# draft3_4lyr_reroute.net
KiCad netlist of a schematic drawn in EAGLE
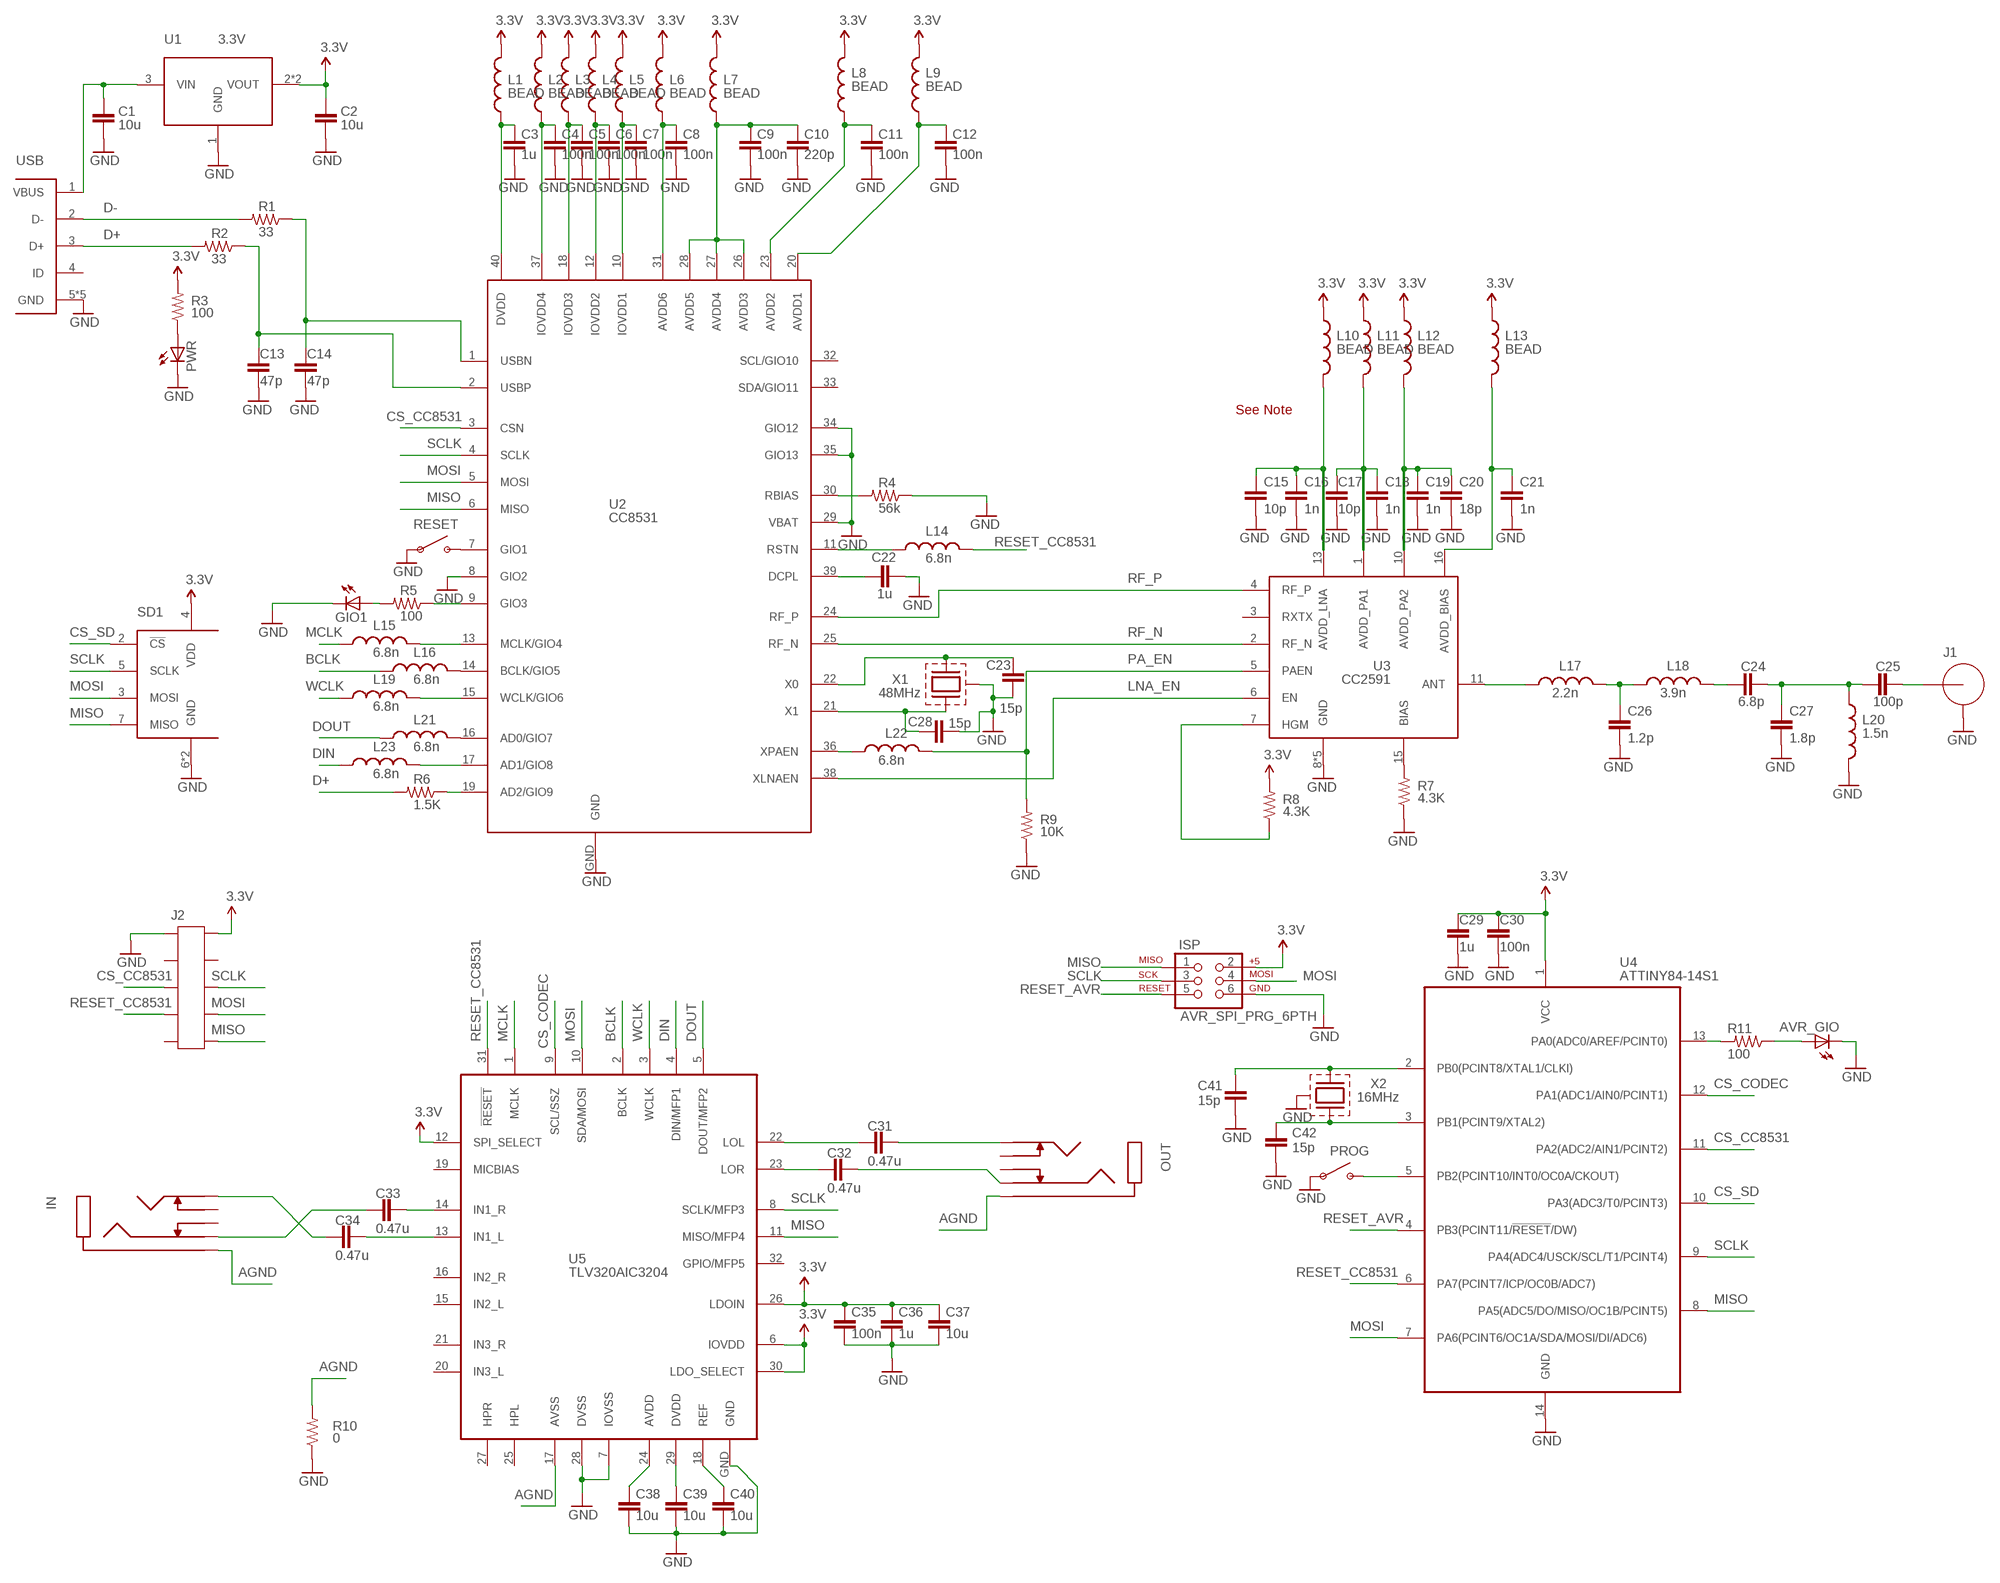
[diagram p0: schematic, sheet 1]

(export (version "E")
  (design (tool "Eeschema 10.0.6"))
  (components
    (comp (ref "AVR_GIO")
      (value "LEDCHIP-LED0603")
      (footprint "eagle-import:CHIP-LED0603")
      (libsource (lib "eagle-import") (part "LEDCHIP-LED0603"))
    )
    (comp (ref "C1")
      (value "10u")
      (footprint "eagle-import:C0603")
      (libsource (lib "eagle-import") (part "C-EUC0603"))
    )
    (comp (ref "C2")
      (value "10u")
      (footprint "eagle-import:C0603")
      (libsource (lib "eagle-import") (part "C-EUC0603"))
    )
    (comp (ref "C3")
      (value "1u")
      (footprint "eagle-import:C0603")
      (libsource (lib "eagle-import") (part "C-EUC0603"))
    )
    (comp (ref "C4")
      (value "100n")
      (footprint "eagle-import:C0603")
      (libsource (lib "eagle-import") (part "C-EUC0603"))
    )
    (comp (ref "C5")
      (value "100n")
      (footprint "eagle-import:C0603")
      (libsource (lib "eagle-import") (part "C-EUC0603"))
    )
    (comp (ref "C6")
      (value "100n")
      (footprint "eagle-import:C0603")
      (libsource (lib "eagle-import") (part "C-EUC0603"))
    )
    (comp (ref "C7")
      (value "100n")
      (footprint "eagle-import:C0603")
      (libsource (lib "eagle-import") (part "C-EUC0603"))
    )
    (comp (ref "C8")
      (value "100n")
      (footprint "eagle-import:C0603")
      (libsource (lib "eagle-import") (part "C-EUC0603"))
    )
    (comp (ref "C9")
      (value "100n")
      (footprint "eagle-import:C0603")
      (libsource (lib "eagle-import") (part "C-EUC0603"))
    )
    (comp (ref "C10")
      (value "220p")
      (footprint "eagle-import:C0603")
      (libsource (lib "eagle-import") (part "C-EUC0603"))
    )
    (comp (ref "C11")
      (value "100n")
      (footprint "eagle-import:C0603")
      (libsource (lib "eagle-import") (part "C-EUC0603"))
    )
    (comp (ref "C12")
      (value "100n")
      (footprint "eagle-import:C0603")
      (libsource (lib "eagle-import") (part "C-EUC0603"))
    )
    (comp (ref "C13")
      (value "47p")
      (footprint "eagle-import:C0603")
      (libsource (lib "eagle-import") (part "C-EUC0603"))
    )
    (comp (ref "C14")
      (value "47p")
      (footprint "eagle-import:C0603")
      (libsource (lib "eagle-import") (part "C-EUC0603"))
    )
    (comp (ref "C15")
      (value "10p")
      (footprint "eagle-import:C0603")
      (libsource (lib "eagle-import") (part "C-EUC0603"))
    )
    (comp (ref "C16")
      (value "1n")
      (footprint "eagle-import:C0603")
      (libsource (lib "eagle-import") (part "C-EUC0603"))
    )
    (comp (ref "C17")
      (value "10p")
      (footprint "eagle-import:C0603")
      (libsource (lib "eagle-import") (part "C-EUC0603"))
    )
    (comp (ref "C18")
      (value "1n")
      (footprint "eagle-import:C0603")
      (libsource (lib "eagle-import") (part "C-EUC0603"))
    )
    (comp (ref "C19")
      (value "1n")
      (footprint "eagle-import:C0603")
      (libsource (lib "eagle-import") (part "C-EUC0603"))
    )
    (comp (ref "C20")
      (value "18p")
      (footprint "eagle-import:C0603")
      (libsource (lib "eagle-import") (part "C-EUC0603"))
    )
    (comp (ref "C21")
      (value "1n")
      (footprint "eagle-import:C0603")
      (libsource (lib "eagle-import") (part "C-EUC0603"))
    )
    (comp (ref "C22")
      (value "1u")
      (footprint "eagle-import:C0603")
      (libsource (lib "eagle-import") (part "C-EUC0603"))
    )
    (comp (ref "C23")
      (value "15p")
      (footprint "eagle-import:C0603")
      (libsource (lib "eagle-import") (part "C-EUC0603"))
    )
    (comp (ref "C24")
      (value "6.8p")
      (footprint "eagle-import:C0603")
      (libsource (lib "eagle-import") (part "C-EUC0603"))
    )
    (comp (ref "C25")
      (value "100p")
      (footprint "eagle-import:C0603")
      (libsource (lib "eagle-import") (part "C-EUC0603"))
    )
    (comp (ref "C26")
      (value "1.2p")
      (footprint "eagle-import:C0603")
      (libsource (lib "eagle-import") (part "C-EUC0603"))
    )
    (comp (ref "C27")
      (value "1.8p")
      (footprint "eagle-import:C0603")
      (libsource (lib "eagle-import") (part "C-EUC0603"))
    )
    (comp (ref "C28")
      (value "15p")
      (footprint "eagle-import:C0603")
      (libsource (lib "eagle-import") (part "C-EUC0603"))
    )
    (comp (ref "C29")
      (value "1u")
      (footprint "eagle-import:C0603")
      (libsource (lib "eagle-import") (part "C-EUC0603"))
    )
    (comp (ref "C30")
      (value "100n")
      (footprint "eagle-import:C0603")
      (libsource (lib "eagle-import") (part "C-EUC0603"))
    )
    (comp (ref "C31")
      (value "0.47u")
      (footprint "eagle-import:C0603")
      (libsource (lib "eagle-import") (part "C-EUC0603"))
    )
    (comp (ref "C32")
      (value "0.47u")
      (footprint "eagle-import:C0603")
      (libsource (lib "eagle-import") (part "C-EUC0603"))
    )
    (comp (ref "C33")
      (value "0.47u")
      (footprint "eagle-import:C0603")
      (libsource (lib "eagle-import") (part "C-EUC0603"))
    )
    (comp (ref "C34")
      (value "0.47u")
      (footprint "eagle-import:C0603")
      (libsource (lib "eagle-import") (part "C-EUC0603"))
    )
    (comp (ref "C35")
      (value "100n")
      (footprint "eagle-import:C0603")
      (libsource (lib "eagle-import") (part "C-EUC0603"))
    )
    (comp (ref "C36")
      (value "1u")
      (footprint "eagle-import:C0603")
      (libsource (lib "eagle-import") (part "C-EUC0603"))
    )
    (comp (ref "C37")
      (value "10u")
      (footprint "eagle-import:C0603")
      (libsource (lib "eagle-import") (part "C-EUC0603"))
    )
    (comp (ref "C38")
      (value "10u")
      (footprint "eagle-import:C0603")
      (libsource (lib "eagle-import") (part "C-EUC0603"))
    )
    (comp (ref "C39")
      (value "10u")
      (footprint "eagle-import:C0603")
      (libsource (lib "eagle-import") (part "C-EUC0603"))
    )
    (comp (ref "C40")
      (value "10u")
      (footprint "eagle-import:C0603")
      (libsource (lib "eagle-import") (part "C-EUC0603"))
    )
    (comp (ref "C41")
      (value "15p")
      (footprint "eagle-import:C0603")
      (libsource (lib "eagle-import") (part "C-EUC0603"))
    )
    (comp (ref "C42")
      (value "15p")
      (footprint "eagle-import:C0603")
      (libsource (lib "eagle-import") (part "C-EUC0603"))
    )
    (comp (ref "GIO1")
      (value "LEDCHIP-LED0603")
      (footprint "eagle-import:CHIP-LED0603")
      (libsource (lib "eagle-import") (part "LEDCHIP-LED0603"))
    )
    (comp (ref "IN")
      (value "PHONE_SW")
      (footprint "eagle-import:35RAPC4BV4")
      (libsource (lib "eagle-import") (part "PHONE_SW"))
    )
    (comp (ref "ISP")
      (value "AVR_SPI_PRG_6PTH")
      (footprint "eagle-import:2X3")
      (libsource (lib "eagle-import") (part "AVR_SPI_PRG_6PTH"))
    )
    (comp (ref "J1")
      (value "SMA")
      (footprint "eagle-import:CONSMA003.031")
      (libsource (lib "eagle-import") (part "SMA"))
    )
    (comp (ref "J2")
      (value "HEADER-10P-SMD-MALE")
      (footprint "eagle-import:10P-0.05-HEADER")
      (libsource (lib "eagle-import") (part "HEADER-10P-SMD-MALE"))
    )
    (comp (ref "L1")
      (value "BEAD")
      (footprint "eagle-import:0603")
      (libsource (lib "eagle-import") (part "INDUCTOR0603"))
    )
    (comp (ref "L2")
      (value "BEAD")
      (footprint "eagle-import:0603")
      (libsource (lib "eagle-import") (part "INDUCTOR0603"))
    )
    (comp (ref "L3")
      (value "BEAD")
      (footprint "eagle-import:0603")
      (libsource (lib "eagle-import") (part "INDUCTOR0603"))
    )
    (comp (ref "L4")
      (value "BEAD")
      (footprint "eagle-import:0603")
      (libsource (lib "eagle-import") (part "INDUCTOR0603"))
    )
    (comp (ref "L5")
      (value "BEAD")
      (footprint "eagle-import:0603")
      (libsource (lib "eagle-import") (part "INDUCTOR0603"))
    )
    (comp (ref "L6")
      (value "BEAD")
      (footprint "eagle-import:0603")
      (libsource (lib "eagle-import") (part "INDUCTOR0603"))
    )
    (comp (ref "L7")
      (value "BEAD")
      (footprint "eagle-import:0603")
      (libsource (lib "eagle-import") (part "INDUCTOR0603"))
    )
    (comp (ref "L8")
      (value "BEAD")
      (footprint "eagle-import:0603")
      (libsource (lib "eagle-import") (part "INDUCTOR0603"))
    )
    (comp (ref "L9")
      (value "BEAD")
      (footprint "eagle-import:0603")
      (libsource (lib "eagle-import") (part "INDUCTOR0603"))
    )
    (comp (ref "L10")
      (value "BEAD")
      (footprint "eagle-import:0603")
      (libsource (lib "eagle-import") (part "INDUCTOR0603"))
    )
    (comp (ref "L11")
      (value "BEAD")
      (footprint "eagle-import:0603")
      (libsource (lib "eagle-import") (part "INDUCTOR0603"))
    )
    (comp (ref "L12")
      (value "BEAD")
      (footprint "eagle-import:0603")
      (libsource (lib "eagle-import") (part "INDUCTOR0603"))
    )
    (comp (ref "L13")
      (value "BEAD")
      (footprint "eagle-import:0603")
      (libsource (lib "eagle-import") (part "INDUCTOR0603"))
    )
    (comp (ref "L14")
      (value "6.8n")
      (footprint "eagle-import:0603")
      (libsource (lib "eagle-import") (part "INDUCTOR0603"))
    )
    (comp (ref "L15")
      (value "6.8n")
      (footprint "eagle-import:0603")
      (libsource (lib "eagle-import") (part "INDUCTOR0603"))
    )
    (comp (ref "L16")
      (value "6.8n")
      (footprint "eagle-import:0603")
      (libsource (lib "eagle-import") (part "INDUCTOR0603"))
    )
    (comp (ref "L17")
      (value "2.2n")
      (footprint "eagle-import:0603")
      (libsource (lib "eagle-import") (part "INDUCTOR0603"))
    )
    (comp (ref "L18")
      (value "3.9n")
      (footprint "eagle-import:0603")
      (libsource (lib "eagle-import") (part "INDUCTOR0603"))
    )
    (comp (ref "L19")
      (value "6.8n")
      (footprint "eagle-import:0603")
      (libsource (lib "eagle-import") (part "INDUCTOR0603"))
    )
    (comp (ref "L20")
      (value "1.5n")
      (footprint "eagle-import:0603")
      (libsource (lib "eagle-import") (part "INDUCTOR0603"))
    )
    (comp (ref "L21")
      (value "6.8n")
      (footprint "eagle-import:0603")
      (libsource (lib "eagle-import") (part "INDUCTOR0603"))
    )
    (comp (ref "L22")
      (value "6.8n")
      (footprint "eagle-import:0603")
      (libsource (lib "eagle-import") (part "INDUCTOR0603"))
    )
    (comp (ref "L23")
      (value "6.8n")
      (footprint "eagle-import:0603")
      (libsource (lib "eagle-import") (part "INDUCTOR0603"))
    )
    (comp (ref "OUT")
      (value "PHONE_SW")
      (footprint "eagle-import:35RAPC4BV4")
      (libsource (lib "eagle-import") (part "PHONE_SW"))
    )
    (comp (ref "PROG")
      (value "SPST-SMD")
      (footprint "eagle-import:TACT_SW")
      (libsource (lib "eagle-import") (part "SPST-SMD"))
    )
    (comp (ref "PWR")
      (value "LEDCHIP-LED0603")
      (footprint "eagle-import:CHIP-LED0603")
      (libsource (lib "eagle-import") (part "LEDCHIP-LED0603"))
    )
    (comp (ref "R1")
      (value "33")
      (footprint "eagle-import:R0603")
      (libsource (lib "eagle-import") (part "R-US_R0603"))
    )
    (comp (ref "R2")
      (value "33")
      (footprint "eagle-import:R0603")
      (libsource (lib "eagle-import") (part "R-US_R0603"))
    )
    (comp (ref "R3")
      (value "100")
      (footprint "eagle-import:R0603")
      (libsource (lib "eagle-import") (part "R-US_R0603"))
    )
    (comp (ref "R4")
      (value "56k")
      (footprint "eagle-import:R0603")
      (libsource (lib "eagle-import") (part "R-US_R0603"))
    )
    (comp (ref "R5")
      (value "100")
      (footprint "eagle-import:R0603")
      (libsource (lib "eagle-import") (part "R-US_R0603"))
    )
    (comp (ref "R6")
      (value "1.5K")
      (footprint "eagle-import:R0603")
      (libsource (lib "eagle-import") (part "R-US_R0603"))
    )
    (comp (ref "R7")
      (value "4.3K")
      (footprint "eagle-import:R0603")
      (libsource (lib "eagle-import") (part "R-US_R0603"))
    )
    (comp (ref "R8")
      (value "4.3K")
      (footprint "eagle-import:R0603")
      (libsource (lib "eagle-import") (part "R-US_R0603"))
    )
    (comp (ref "R9")
      (value "10K")
      (footprint "eagle-import:R0603")
      (libsource (lib "eagle-import") (part "R-US_R0603"))
    )
    (comp (ref "R10")
      (value "0")
      (footprint "eagle-import:R0603")
      (libsource (lib "eagle-import") (part "R-US_R0603"))
    )
    (comp (ref "R11")
      (value "100")
      (footprint "eagle-import:R0603")
      (libsource (lib "eagle-import") (part "R-US_R0603"))
    )
    (comp (ref "RESET")
      (value "SPST-SMD")
      (footprint "eagle-import:TACT_SW")
      (libsource (lib "eagle-import") (part "SPST-SMD"))
    )
    (comp (ref "SD1")
      (value "MICROSDDM3AT")
      (footprint "eagle-import:DM3AT")
      (libsource (lib "eagle-import") (part "MICROSDDM3AT"))
    )
    (comp (ref "U1")
      (value "3.3V")
      (footprint "eagle-import:SOT-223")
      (libsource (lib "eagle-import") (part "NX1117C"))
    )
    (comp (ref "U2")
      (value "CC8531")
      (footprint "eagle-import:S-PVQFN-N40")
      (libsource (lib "eagle-import") (part "CC8531"))
    )
    (comp (ref "U3")
      (value "CC2591")
      (footprint "eagle-import:S-PVQFN-N16")
      (libsource (lib "eagle-import") (part "CC2591"))
    )
    (comp (ref "U4")
      (value "ATTINY84-14S1")
      (footprint "eagle-import:SOIC14")
      (libsource (lib "eagle-import") (part "ATTINY84-14S1"))
    )
    (comp (ref "U5")
      (value "TLV320AIC3204")
      (footprint "eagle-import:S-PVQFN-N32")
      (libsource (lib "eagle-import") (part "TLV320AIC3204"))
    )
    (comp (ref "USB")
      (value "USB_MICRO_AB")
      (footprint "eagle-import:USB_MICRO_AB")
      (libsource (lib "eagle-import") (part "USB_MICRO_AB"))
    )
    (comp (ref "X1")
      (value "48MHz")
      (footprint "eagle-import:ABM3C")
      (libsource (lib "eagle-import") (part "XTAL-ABRACONABM3C"))
    )
    (comp (ref "X2")
      (value "16MHz")
      (footprint "eagle-import:ABMM")
      (libsource (lib "eagle-import") (part "XTAL-ABRACONABMM"))
    )
  )
  (nets
    (net (code "1") (name "/AGND") (class "Default")
      (node (ref "IN") (pin "1") (pinfunction "GND_1") (pintype "bidirectional"))
      (node (ref "OUT") (pin "1") (pinfunction "GND_1") (pintype "bidirectional"))
      (node (ref "R10") (pin "2") (pinfunction "2_2") (pintype "passive"))
      (node (ref "U5") (pin "17") (pinfunction "AVSS_17") (pintype "bidirectional"))
    )
    (net (code "2") (name "/BCLK") (class "Default")
      (node (ref "L16") (pin "1") (pinfunction "1_1") (pintype "passive"))
      (node (ref "U5") (pin "2") (pinfunction "BCLK_2") (pintype "bidirectional"))
    )
    (net (code "3") (name "/CS_CC8531") (class "Default")
      (node (ref "J2") (pin "5") (pinfunction "5_5") (pintype "bidirectional"))
      (node (ref "U2") (pin "3") (pinfunction "CSN_3") (pintype "bidirectional"))
      (node (ref "U4") (pin "11") (pinfunction "PA2(ADC2/AIN1/PCINT2)_11") (pintype "bidirectional"))
    )
    (net (code "4") (name "/CS_CODEC") (class "Default")
      (node (ref "U4") (pin "12") (pinfunction "PA1(ADC1/AIN0/PCINT1)_12") (pintype "bidirectional"))
      (node (ref "U5") (pin "9") (pinfunction "SCL/SSZ_9") (pintype "bidirectional"))
    )
    (net (code "5") (name "/CS_SD") (class "Default")
      (node (ref "SD1") (pin "2") (pinfunction "~{CS}_2") (pintype "bidirectional"))
      (node (ref "U4") (pin "10") (pinfunction "PA3(ADC3/T0/PCINT3)_10") (pintype "bidirectional"))
    )
    (net (code "6") (name "/D+") (class "Default")
      (node (ref "R2") (pin "2") (pinfunction "2_2") (pintype "passive"))
      (node (ref "R6") (pin "2") (pinfunction "2_2") (pintype "passive"))
      (node (ref "USB") (pin "3") (pinfunction "D+_3") (pintype "bidirectional"))
    )
    (net (code "7") (name "/D-") (class "Default")
      (node (ref "R1") (pin "2") (pinfunction "2_2") (pintype "passive"))
      (node (ref "USB") (pin "2") (pinfunction "D-_2") (pintype "bidirectional"))
    )
    (net (code "8") (name "/DIN") (class "Default")
      (node (ref "L23") (pin "1") (pinfunction "1_1") (pintype "passive"))
      (node (ref "U5") (pin "4") (pinfunction "DIN/MFP1_4") (pintype "bidirectional"))
    )
    (net (code "9") (name "/DOUT") (class "Default")
      (node (ref "L21") (pin "1") (pinfunction "1_1") (pintype "passive"))
      (node (ref "U5") (pin "5") (pinfunction "DOUT/MFP2_5") (pintype "bidirectional"))
    )
    (net (code "10") (name "/LNA_EN") (class "Default")
      (node (ref "U2") (pin "38") (pinfunction "XLNAEN_38") (pintype "bidirectional"))
      (node (ref "U3") (pin "6") (pinfunction "EN_6") (pintype "bidirectional"))
    )
    (net (code "11") (name "/MCLK") (class "Default")
      (node (ref "L15") (pin "1") (pinfunction "1_1") (pintype "passive"))
      (node (ref "U5") (pin "1") (pinfunction "MCLK_1") (pintype "bidirectional"))
    )
    (net (code "12") (name "/MISO") (class "Default")
      (node (ref "ISP") (pin "1") (pinfunction "1_1") (pintype "passive"))
      (node (ref "J2") (pin "10") (pinfunction "10_10") (pintype "bidirectional"))
      (node (ref "SD1") (pin "7") (pinfunction "MISO_7") (pintype "bidirectional"))
      (node (ref "U2") (pin "6") (pinfunction "MISO_6") (pintype "bidirectional"))
      (node (ref "U4") (pin "8") (pinfunction "PA5(ADC5/DO/MISO/OC1B/PCINT5)_8") (pintype "bidirectional"))
      (node (ref "U5") (pin "11") (pinfunction "MISO/MFP4_11") (pintype "bidirectional"))
    )
    (net (code "13") (name "/MOSI") (class "Default")
      (node (ref "ISP") (pin "4") (pinfunction "4_4") (pintype "passive"))
      (node (ref "J2") (pin "8") (pinfunction "8_8") (pintype "bidirectional"))
      (node (ref "SD1") (pin "3") (pinfunction "MOSI_3") (pintype "bidirectional"))
      (node (ref "U2") (pin "5") (pinfunction "MOSI_5") (pintype "bidirectional"))
      (node (ref "U4") (pin "7") (pinfunction "PA6(PCINT6/OC1A/SDA/MOSI/DI/ADC6)_7") (pintype "bidirectional"))
      (node (ref "U5") (pin "10") (pinfunction "SDA/MOSI_10") (pintype "bidirectional"))
    )
    (net (code "14") (name "/PA_EN") (class "Default")
      (node (ref "L22") (pin "2") (pinfunction "2_2") (pintype "passive"))
      (node (ref "R9") (pin "2") (pinfunction "2_2") (pintype "passive"))
      (node (ref "U3") (pin "5") (pinfunction "PAEN_5") (pintype "bidirectional"))
    )
    (net (code "15") (name "/RESET_AVR") (class "Default")
      (node (ref "ISP") (pin "5") (pinfunction "5_5") (pintype "passive"))
      (node (ref "U4") (pin "4") (pinfunction "PB3(PCINT11/~{RESET}/DW)_4") (pintype "bidirectional"))
    )
    (net (code "16") (name "/RESET_CC8531") (class "Default")
      (node (ref "J2") (pin "7") (pinfunction "7_7") (pintype "bidirectional"))
      (node (ref "L14") (pin "2") (pinfunction "2_2") (pintype "passive"))
      (node (ref "U4") (pin "6") (pinfunction "PA7(PCINT7/ICP/OC0B/ADC7)_6") (pintype "bidirectional"))
      (node (ref "U5") (pin "31") (pinfunction "~{RESET}_31") (pintype "bidirectional"))
    )
    (net (code "17") (name "/RF_N") (class "Default")
      (node (ref "U2") (pin "25") (pinfunction "RF_N_25") (pintype "bidirectional"))
      (node (ref "U3") (pin "2") (pinfunction "RF_N_2") (pintype "bidirectional"))
    )
    (net (code "18") (name "/RF_P") (class "Default")
      (node (ref "U2") (pin "24") (pinfunction "RF_P_24") (pintype "bidirectional"))
      (node (ref "U3") (pin "4") (pinfunction "RF_P_4") (pintype "bidirectional"))
    )
    (net (code "19") (name "/SCLK") (class "Default")
      (node (ref "ISP") (pin "3") (pinfunction "3_3") (pintype "passive"))
      (node (ref "J2") (pin "6") (pinfunction "6_6") (pintype "bidirectional"))
      (node (ref "SD1") (pin "5") (pinfunction "SCLK_5") (pintype "bidirectional"))
      (node (ref "U2") (pin "4") (pinfunction "SCLK_4") (pintype "bidirectional"))
      (node (ref "U4") (pin "9") (pinfunction "PA4(ADC4/USCK/SCL/T1/PCINT4)_9") (pintype "bidirectional"))
      (node (ref "U5") (pin "8") (pinfunction "SCLK/MFP3_8") (pintype "bidirectional"))
    )
    (net (code "20") (name "/WCLK") (class "Default")
      (node (ref "L19") (pin "1") (pinfunction "1_1") (pintype "passive"))
      (node (ref "U5") (pin "3") (pinfunction "WCLK_3") (pintype "bidirectional"))
    )
    (net (code "21") (name "3.3V") (class "Default")
      (node (ref "C2") (pin "1") (pinfunction "1_1") (pintype "passive"))
      (node (ref "C29") (pin "1") (pinfunction "1_1") (pintype "passive"))
      (node (ref "C30") (pin "1") (pinfunction "1_1") (pintype "passive"))
      (node (ref "C35") (pin "1") (pinfunction "1_1") (pintype "passive"))
      (node (ref "C36") (pin "1") (pinfunction "1_1") (pintype "passive"))
      (node (ref "C37") (pin "1") (pinfunction "1_1") (pintype "passive"))
      (node (ref "ISP") (pin "2") (pinfunction "2_2") (pintype "passive"))
      (node (ref "J2") (pin "2") (pinfunction "2_2") (pintype "bidirectional"))
      (node (ref "L1") (pin "2") (pinfunction "2_2") (pintype "passive"))
      (node (ref "L10") (pin "1") (pinfunction "1_1") (pintype "passive"))
      (node (ref "L11") (pin "1") (pinfunction "1_1") (pintype "passive"))
      (node (ref "L12") (pin "1") (pinfunction "1_1") (pintype "passive"))
      (node (ref "L13") (pin "1") (pinfunction "1_1") (pintype "passive"))
      (node (ref "L2") (pin "2") (pinfunction "2_2") (pintype "passive"))
      (node (ref "L3") (pin "2") (pinfunction "2_2") (pintype "passive"))
      (node (ref "L4") (pin "2") (pinfunction "2_2") (pintype "passive"))
      (node (ref "L5") (pin "2") (pinfunction "2_2") (pintype "passive"))
      (node (ref "L6") (pin "2") (pinfunction "2_2") (pintype "passive"))
      (node (ref "L7") (pin "2") (pinfunction "2_2") (pintype "passive"))
      (node (ref "L8") (pin "2") (pinfunction "2_2") (pintype "passive"))
      (node (ref "L9") (pin "2") (pinfunction "2_2") (pintype "passive"))
      (node (ref "R3") (pin "2") (pinfunction "2_2") (pintype "passive"))
      (node (ref "R8") (pin "2") (pinfunction "2_2") (pintype "passive"))
      (node (ref "SD1") (pin "4") (pinfunction "VDD_4") (pintype "bidirectional"))
      (node (ref "U1") (pin "2") (pinfunction "VOUT_2") (pintype "bidirectional"))
      (node (ref "U1") (pin "4") (pinfunction "VOUT_4") (pintype "bidirectional"))
      (node (ref "U4") (pin "1") (pinfunction "VCC_1") (pintype "bidirectional"))
      (node (ref "U5") (pin "12") (pinfunction "SPI_SELECT_12") (pintype "bidirectional"))
      (node (ref "U5") (pin "26") (pinfunction "LDOIN_26") (pintype "bidirectional"))
      (node (ref "U5") (pin "30") (pinfunction "LDO_SELECT_30") (pintype "bidirectional"))
      (node (ref "U5") (pin "6") (pinfunction "IOVDD_6") (pintype "bidirectional"))
    )
    (net (code "22") (name "GND") (class "Default")
      (node (ref "AVR_GIO") (pin "C") (pinfunction "C_C") (pintype "passive"))
      (node (ref "C1") (pin "2") (pinfunction "2_2") (pintype "passive"))
      (node (ref "C10") (pin "2") (pinfunction "2_2") (pintype "passive"))
      (node (ref "C11") (pin "2") (pinfunction "2_2") (pintype "passive"))
      (node (ref "C12") (pin "2") (pinfunction "2_2") (pintype "passive"))
      (node (ref "C13") (pin "2") (pinfunction "2_2") (pintype "passive"))
      (node (ref "C14") (pin "2") (pinfunction "2_2") (pintype "passive"))
      (node (ref "C15") (pin "2") (pinfunction "2_2") (pintype "passive"))
      (node (ref "C16") (pin "2") (pinfunction "2_2") (pintype "passive"))
      (node (ref "C17") (pin "2") (pinfunction "2_2") (pintype "passive"))
      (node (ref "C18") (pin "2") (pinfunction "2_2") (pintype "passive"))
      (node (ref "C19") (pin "2") (pinfunction "2_2") (pintype "passive"))
      (node (ref "C2") (pin "2") (pinfunction "2_2") (pintype "passive"))
      (node (ref "C20") (pin "2") (pinfunction "2_2") (pintype "passive"))
      (node (ref "C21") (pin "2") (pinfunction "2_2") (pintype "passive"))
      (node (ref "C22") (pin "2") (pinfunction "2_2") (pintype "passive"))
      (node (ref "C23") (pin "2") (pinfunction "2_2") (pintype "passive"))
      (node (ref "C26") (pin "2") (pinfunction "2_2") (pintype "passive"))
      (node (ref "C27") (pin "2") (pinfunction "2_2") (pintype "passive"))
      (node (ref "C28") (pin "2") (pinfunction "2_2") (pintype "passive"))
      (node (ref "C29") (pin "2") (pinfunction "2_2") (pintype "passive"))
      (node (ref "C3") (pin "2") (pinfunction "2_2") (pintype "passive"))
      (node (ref "C30") (pin "2") (pinfunction "2_2") (pintype "passive"))
      (node (ref "C35") (pin "2") (pinfunction "2_2") (pintype "passive"))
      (node (ref "C36") (pin "2") (pinfunction "2_2") (pintype "passive"))
      (node (ref "C37") (pin "2") (pinfunction "2_2") (pintype "passive"))
      (node (ref "C38") (pin "2") (pinfunction "2_2") (pintype "passive"))
      (node (ref "C39") (pin "2") (pinfunction "2_2") (pintype "passive"))
      (node (ref "C4") (pin "2") (pinfunction "2_2") (pintype "passive"))
      (node (ref "C40") (pin "2") (pinfunction "2_2") (pintype "passive"))
      (node (ref "C41") (pin "1") (pinfunction "1_1") (pintype "passive"))
      (node (ref "C42") (pin "1") (pinfunction "1_1") (pintype "passive"))
      (node (ref "C5") (pin "2") (pinfunction "2_2") (pintype "passive"))
      (node (ref "C6") (pin "2") (pinfunction "2_2") (pintype "passive"))
      (node (ref "C7") (pin "2") (pinfunction "2_2") (pintype "passive"))
      (node (ref "C8") (pin "2") (pinfunction "2_2") (pintype "passive"))
      (node (ref "C9") (pin "2") (pinfunction "2_2") (pintype "passive"))
      (node (ref "GIO1") (pin "C") (pinfunction "C_C") (pintype "passive"))
      (node (ref "ISP") (pin "6") (pinfunction "6_6") (pintype "passive"))
      (node (ref "J1") (pin "GND1") (pinfunction "GND_GND1") (pintype "bidirectional"))
      (node (ref "J1") (pin "GND2") (pinfunction "GND_GND2") (pintype "bidirectional"))
      (node (ref "J1") (pin "GND3") (pinfunction "GND_GND3") (pintype "bidirectional"))
      (node (ref "J1") (pin "GND4") (pinfunction "GND_GND4") (pintype "bidirectional"))
      (node (ref "J2") (pin "1") (pinfunction "1_1") (pintype "bidirectional"))
      (node (ref "L20") (pin "2") (pinfunction "2_2") (pintype "passive"))
      (node (ref "PROG") (pin "1") (pinfunction "P$1_1") (pintype "bidirectional"))
      (node (ref "PROG") (pin "2") (pinfunction "P$1_2") (pintype "bidirectional"))
      (node (ref "PWR") (pin "C") (pinfunction "C_C") (pintype "passive"))
      (node (ref "R10") (pin "1") (pinfunction "1_1") (pintype "passive"))
      (node (ref "R4") (pin "1") (pinfunction "1_1") (pintype "passive"))
      (node (ref "R7") (pin "1") (pinfunction "1_1") (pintype "passive"))
      (node (ref "R9") (pin "1") (pinfunction "1_1") (pintype "passive"))
      (node (ref "RESET") (pin "1") (pinfunction "P$1_1") (pintype "bidirectional"))
      (node (ref "RESET") (pin "2") (pinfunction "P$1_2") (pintype "bidirectional"))
      (node (ref "SD1") (pin "6") (pinfunction "GND_6") (pintype "bidirectional"))
      (node (ref "SD1") (pin "GND") (pinfunction "GND_GND") (pintype "bidirectional"))
      (node (ref "U1") (pin "1") (pinfunction "GND_1") (pintype "bidirectional"))
      (node (ref "U2") (pin "29") (pinfunction "VBAT_29") (pintype "bidirectional"))
      (node (ref "U2") (pin "34") (pinfunction "GIO12_34") (pintype "bidirectional"))
      (node (ref "U2") (pin "35") (pinfunction "GIO13_35") (pintype "bidirectional"))
      (node (ref "U2") (pin "8") (pinfunction "GIO2_8") (pintype "bidirectional"))
      (node (ref "U2") (pin "GND") (pinfunction "GND_GND") (pintype "bidirectional"))
      (node (ref "U3") (pin "12") (pinfunction "GND_12") (pintype "bidirectional"))
      (node (ref "U3") (pin "14") (pinfunction "GND_14") (pintype "bidirectional"))
      (node (ref "U3") (pin "8") (pinfunction "GND_8") (pintype "bidirectional"))
      (node (ref "U3") (pin "9") (pinfunction "GND_9") (pintype "bidirectional"))
      (node (ref "U3") (pin "GND") (pinfunction "GND_GND") (pintype "bidirectional"))
      (node (ref "U4") (pin "14") (pinfunction "GND_14") (pintype "bidirectional"))
      (node (ref "U5") (pin "28") (pinfunction "DVSS_28") (pintype "bidirectional"))
      (node (ref "U5") (pin "7") (pinfunction "IOVSS_7") (pintype "bidirectional"))
      (node (ref "U5") (pin "GND") (pinfunction "GND_GND") (pintype "bidirectional"))
      (node (ref "USB") (pin "5") (pinfunction "GND_5") (pintype "bidirectional"))
      (node (ref "USB") (pin "GND1") (pinfunction "GND_GND1") (pintype "bidirectional"))
      (node (ref "USB") (pin "GND2") (pinfunction "GND_GND2") (pintype "bidirectional"))
      (node (ref "USB") (pin "GND3") (pinfunction "GND_GND3") (pintype "bidirectional"))
      (node (ref "USB") (pin "GND4") (pinfunction "GND_GND4") (pintype "bidirectional"))
      (node (ref "X1") (pin "2") (pinfunction "CASE_2") (pintype "passive"))
      (node (ref "X1") (pin "4") (pinfunction "CASE_4") (pintype "passive"))
      (node (ref "X2") (pin "2") (pinfunction "CASE_2") (pintype "passive"))
      (node (ref "X2") (pin "4") (pinfunction "CASE_4") (pintype "passive"))
    )
    (net (code "23") (name "Net-(AVR_GIO-PadA)") (class "Default")
      (node (ref "AVR_GIO") (pin "A") (pinfunction "A_A") (pintype "passive"))
      (node (ref "R11") (pin "1") (pinfunction "1_1") (pintype "passive"))
    )
    (net (code "24") (name "Net-(C24-Pad1)") (class "Default")
      (node (ref "C24") (pin "1") (pinfunction "1_1") (pintype "passive"))
      (node (ref "L18") (pin "2") (pinfunction "2_2") (pintype "passive"))
    )
    (net (code "25") (name "Net-(C24-Pad2)") (class "Default")
      (node (ref "C24") (pin "2") (pinfunction "2_2") (pintype "passive"))
      (node (ref "C25") (pin "1") (pinfunction "1_1") (pintype "passive"))
      (node (ref "C27") (pin "1") (pinfunction "1_1") (pintype "passive"))
      (node (ref "L20") (pin "1") (pinfunction "1_1") (pintype "passive"))
    )
    (net (code "26") (name "Net-(C25-Pad2)") (class "Default")
      (node (ref "C25") (pin "2") (pinfunction "2_2") (pintype "passive"))
      (node (ref "J1") (pin "SIG") (pinfunction "SIG_SIG") (pintype "bidirectional"))
    )
    (net (code "27") (name "Net-(C26-Pad1)") (class "Default")
      (node (ref "C26") (pin "1") (pinfunction "1_1") (pintype "passive"))
      (node (ref "L17") (pin "2") (pinfunction "2_2") (pintype "passive"))
      (node (ref "L18") (pin "1") (pinfunction "1_1") (pintype "passive"))
    )
    (net (code "28") (name "Net-(GIO1-PadA)") (class "Default")
      (node (ref "GIO1") (pin "A") (pinfunction "A_A") (pintype "passive"))
      (node (ref "R5") (pin "2") (pinfunction "2_2") (pintype "passive"))
    )
    (net (code "29") (name "Net-(IN-L)") (class "Default")
      (node (ref "C34") (pin "1") (pinfunction "1_1") (pintype "passive"))
      (node (ref "IN") (pin "2") (pinfunction "L_2") (pintype "bidirectional"))
    )
    (net (code "30") (name "Net-(IN-R)") (class "Default")
      (node (ref "C33") (pin "1") (pinfunction "1_1") (pintype "passive"))
      (node (ref "IN") (pin "4") (pinfunction "R_4") (pintype "bidirectional"))
    )
    (net (code "31") (name "Net-(OUT-L)") (class "Default")
      (node (ref "C31") (pin "2") (pinfunction "2_2") (pintype "passive"))
      (node (ref "OUT") (pin "2") (pinfunction "L_2") (pintype "bidirectional"))
    )
    (net (code "32") (name "Net-(OUT-R)") (class "Default")
      (node (ref "C32") (pin "2") (pinfunction "2_2") (pintype "passive"))
      (node (ref "OUT") (pin "4") (pinfunction "R_4") (pintype "bidirectional"))
    )
    (net (code "33") (name "Net-(PWR-PadA)") (class "Default")
      (node (ref "PWR") (pin "A") (pinfunction "A_A") (pintype "passive"))
      (node (ref "R3") (pin "1") (pinfunction "1_1") (pintype "passive"))
    )
    (net (code "34") (name "Net-(U1-VIN)") (class "Default")
      (node (ref "C1") (pin "1") (pinfunction "1_1") (pintype "passive"))
      (node (ref "U1") (pin "3") (pinfunction "VIN_3") (pintype "bidirectional"))
      (node (ref "USB") (pin "1") (pinfunction "VBUS_1") (pintype "bidirectional"))
    )
    (net (code "35") (name "Net-(U2-AD0{slash}GIO7)") (class "Default")
      (node (ref "L21") (pin "2") (pinfunction "2_2") (pintype "passive"))
      (node (ref "U2") (pin "16") (pinfunction "AD0/GIO7_16") (pintype "bidirectional"))
    )
    (net (code "36") (name "Net-(U2-AD1{slash}GIO8)") (class "Default")
      (node (ref "L23") (pin "2") (pinfunction "2_2") (pintype "passive"))
      (node (ref "U2") (pin "17") (pinfunction "AD1/GIO8_17") (pintype "bidirectional"))
    )
    (net (code "37") (name "Net-(U2-AD2{slash}GIO9)") (class "Default")
      (node (ref "R6") (pin "1") (pinfunction "1_1") (pintype "passive"))
      (node (ref "U2") (pin "19") (pinfunction "AD2/GIO9_19") (pintype "bidirectional"))
    )
    (net (code "38") (name "Net-(U2-AVDD1)") (class "Default")
      (node (ref "C12") (pin "1") (pinfunction "1_1") (pintype "passive"))
      (node (ref "L9") (pin "1") (pinfunction "1_1") (pintype "passive"))
      (node (ref "U2") (pin "20") (pinfunction "AVDD1_20") (pintype "bidirectional"))
    )
    (net (code "39") (name "Net-(U2-AVDD2)") (class "Default")
      (node (ref "C11") (pin "1") (pinfunction "1_1") (pintype "passive"))
      (node (ref "L8") (pin "1") (pinfunction "1_1") (pintype "passive"))
      (node (ref "U2") (pin "23") (pinfunction "AVDD2_23") (pintype "bidirectional"))
    )
    (net (code "40") (name "Net-(U2-AVDD3)") (class "Default")
      (node (ref "C10") (pin "1") (pinfunction "1_1") (pintype "passive"))
      (node (ref "C9") (pin "1") (pinfunction "1_1") (pintype "passive"))
      (node (ref "L7") (pin "1") (pinfunction "1_1") (pintype "passive"))
      (node (ref "U2") (pin "26") (pinfunction "AVDD3_26") (pintype "bidirectional"))
      (node (ref "U2") (pin "27") (pinfunction "AVDD4_27") (pintype "bidirectional"))
      (node (ref "U2") (pin "28") (pinfunction "AVDD5_28") (pintype "bidirectional"))
    )
    (net (code "41") (name "Net-(U2-AVDD6)") (class "Default")
      (node (ref "C8") (pin "1") (pinfunction "1_1") (pintype "passive"))
      (node (ref "L6") (pin "1") (pinfunction "1_1") (pintype "passive"))
      (node (ref "U2") (pin "31") (pinfunction "AVDD6_31") (pintype "bidirectional"))
    )
    (net (code "42") (name "Net-(U2-BCLK{slash}GIO5)") (class "Default")
      (node (ref "L16") (pin "2") (pinfunction "2_2") (pintype "passive"))
      (node (ref "U2") (pin "14") (pinfunction "BCLK/GIO5_14") (pintype "bidirectional"))
    )
    (net (code "43") (name "Net-(U2-DCPL)") (class "Default")
      (node (ref "C22") (pin "1") (pinfunction "1_1") (pintype "passive"))
      (node (ref "U2") (pin "39") (pinfunction "DCPL_39") (pintype "bidirectional"))
    )
    (net (code "44") (name "Net-(U2-DVDD)") (class "Default")
      (node (ref "C3") (pin "1") (pinfunction "1_1") (pintype "passive"))
      (node (ref "L1") (pin "1") (pinfunction "1_1") (pintype "passive"))
      (node (ref "U2") (pin "40") (pinfunction "DVDD_40") (pintype "bidirectional"))
    )
    (net (code "45") (name "Net-(U2-GIO1)") (class "Default")
      (node (ref "RESET") (pin "3") (pinfunction "P$2_3") (pintype "bidirectional"))
      (node (ref "RESET") (pin "4") (pinfunction "P$2_4") (pintype "bidirectional"))
      (node (ref "U2") (pin "7") (pinfunction "GIO1_7") (pintype "bidirectional"))
    )
    (net (code "46") (name "Net-(U2-GIO3)") (class "Default")
      (node (ref "R5") (pin "1") (pinfunction "1_1") (pintype "passive"))
      (node (ref "U2") (pin "9") (pinfunction "GIO3_9") (pintype "bidirectional"))
    )
    (net (code "47") (name "Net-(U2-IOVDD1)") (class "Default")
      (node (ref "C7") (pin "1") (pinfunction "1_1") (pintype "passive"))
      (node (ref "L5") (pin "1") (pinfunction "1_1") (pintype "passive"))
      (node (ref "U2") (pin "10") (pinfunction "IOVDD1_10") (pintype "bidirectional"))
    )
    (net (code "48") (name "Net-(U2-IOVDD2)") (class "Default")
      (node (ref "C6") (pin "1") (pinfunction "1_1") (pintype "passive"))
      (node (ref "L4") (pin "1") (pinfunction "1_1") (pintype "passive"))
      (node (ref "U2") (pin "12") (pinfunction "IOVDD2_12") (pintype "bidirectional"))
    )
    (net (code "49") (name "Net-(U2-IOVDD3)") (class "Default")
      (node (ref "C5") (pin "1") (pinfunction "1_1") (pintype "passive"))
      (node (ref "L3") (pin "1") (pinfunction "1_1") (pintype "passive"))
      (node (ref "U2") (pin "18") (pinfunction "IOVDD3_18") (pintype "bidirectional"))
    )
    (net (code "50") (name "Net-(U2-IOVDD4)") (class "Default")
      (node (ref "C4") (pin "1") (pinfunction "1_1") (pintype "passive"))
      (node (ref "L2") (pin "1") (pinfunction "1_1") (pintype "passive"))
      (node (ref "U2") (pin "37") (pinfunction "IOVDD4_37") (pintype "bidirectional"))
    )
    (net (code "51") (name "Net-(U2-MCLK{slash}GIO4)") (class "Default")
      (node (ref "L15") (pin "2") (pinfunction "2_2") (pintype "passive"))
      (node (ref "U2") (pin "13") (pinfunction "MCLK/GIO4_13") (pintype "bidirectional"))
    )
    (net (code "52") (name "Net-(U2-RBIAS)") (class "Default")
      (node (ref "R4") (pin "2") (pinfunction "2_2") (pintype "passive"))
      (node (ref "U2") (pin "30") (pinfunction "RBIAS_30") (pintype "bidirectional"))
    )
    (net (code "53") (name "Net-(U2-RSTN)") (class "Default")
      (node (ref "L14") (pin "1") (pinfunction "1_1") (pintype "passive"))
      (node (ref "U2") (pin "11") (pinfunction "RSTN_11") (pintype "bidirectional"))
    )
    (net (code "54") (name "Net-(U2-USBN)") (class "Default")
      (node (ref "C14") (pin "1") (pinfunction "1_1") (pintype "passive"))
      (node (ref "R1") (pin "1") (pinfunction "1_1") (pintype "passive"))
      (node (ref "U2") (pin "1") (pinfunction "USBN_1") (pintype "bidirectional"))
    )
    (net (code "55") (name "Net-(U2-USBP)") (class "Default")
      (node (ref "C13") (pin "1") (pinfunction "1_1") (pintype "passive"))
      (node (ref "R2") (pin "1") (pinfunction "1_1") (pintype "passive"))
      (node (ref "U2") (pin "2") (pinfunction "USBP_2") (pintype "bidirectional"))
    )
    (net (code "56") (name "Net-(U2-WCLK{slash}GIO6)") (class "Default")
      (node (ref "L19") (pin "2") (pinfunction "2_2") (pintype "passive"))
      (node (ref "U2") (pin "15") (pinfunction "WCLK/GIO6_15") (pintype "bidirectional"))
    )
    (net (code "57") (name "Net-(U2-X0)") (class "Default")
      (node (ref "C23") (pin "1") (pinfunction "1_1") (pintype "passive"))
      (node (ref "U2") (pin "22") (pinfunction "X0_22") (pintype "bidirectional"))
      (node (ref "X1") (pin "3") (pinfunction "2_3") (pintype "passive"))
    )
    (net (code "58") (name "Net-(U2-X1)") (class "Default")
      (node (ref "C28") (pin "1") (pinfunction "1_1") (pintype "passive"))
      (node (ref "U2") (pin "21") (pinfunction "X1_21") (pintype "bidirectional"))
      (node (ref "X1") (pin "1") (pinfunction "1_1") (pintype "passive"))
    )
    (net (code "59") (name "Net-(U2-XPAEN)") (class "Default")
      (node (ref "L22") (pin "1") (pinfunction "1_1") (pintype "passive"))
      (node (ref "U2") (pin "36") (pinfunction "XPAEN_36") (pintype "bidirectional"))
    )
    (net (code "60") (name "Net-(U3-ANT)") (class "Default")
      (node (ref "L17") (pin "1") (pinfunction "1_1") (pintype "passive"))
      (node (ref "U3") (pin "11") (pinfunction "ANT_11") (pintype "bidirectional"))
    )
    (net (code "61") (name "Net-(U3-AVDD_BIAS)") (class "Default")
      (node (ref "C21") (pin "1") (pinfunction "1_1") (pintype "passive"))
      (node (ref "L13") (pin "2") (pinfunction "2_2") (pintype "passive"))
      (node (ref "U3") (pin "16") (pinfunction "AVDD_BIAS_16") (pintype "bidirectional"))
    )
    (net (code "62") (name "Net-(U3-AVDD_LNA)") (class "Default")
      (node (ref "C15") (pin "1") (pinfunction "1_1") (pintype "passive"))
      (node (ref "C16") (pin "1") (pinfunction "1_1") (pintype "passive"))
      (node (ref "L10") (pin "2") (pinfunction "2_2") (pintype "passive"))
      (node (ref "U3") (pin "13") (pinfunction "AVDD_LNA_13") (pintype "bidirectional"))
    )
    (net (code "63") (name "Net-(U3-AVDD_PA1)") (class "Default")
      (node (ref "C17") (pin "1") (pinfunction "1_1") (pintype "passive"))
      (node (ref "C18") (pin "1") (pinfunction "1_1") (pintype "passive"))
      (node (ref "L11") (pin "2") (pinfunction "2_2") (pintype "passive"))
      (node (ref "U3") (pin "1") (pinfunction "AVDD_PA1_1") (pintype "bidirectional"))
    )
    (net (code "64") (name "Net-(U3-AVDD_PA2)") (class "Default")
      (node (ref "C19") (pin "1") (pinfunction "1_1") (pintype "passive"))
      (node (ref "C20") (pin "1") (pinfunction "1_1") (pintype "passive"))
      (node (ref "L12") (pin "2") (pinfunction "2_2") (pintype "passive"))
      (node (ref "U3") (pin "10") (pinfunction "AVDD_PA2_10") (pintype "bidirectional"))
    )
    (net (code "65") (name "Net-(U3-BIAS)") (class "Default")
      (node (ref "R7") (pin "2") (pinfunction "2_2") (pintype "passive"))
      (node (ref "U3") (pin "15") (pinfunction "BIAS_15") (pintype "bidirectional"))
    )
    (net (code "66") (name "Net-(U3-HGM)") (class "Default")
      (node (ref "R8") (pin "1") (pinfunction "1_1") (pintype "passive"))
      (node (ref "U3") (pin "7") (pinfunction "HGM_7") (pintype "bidirectional"))
    )
    (net (code "67") (name "Net-(U4-PA0(ADC0{slash}AREF{slash}PCINT0))") (class "Default")
      (node (ref "R11") (pin "2") (pinfunction "2_2") (pintype "passive"))
      (node (ref "U4") (pin "13") (pinfunction "PA0(ADC0/AREF/PCINT0)_13") (pintype "bidirectional"))
    )
    (net (code "68") (name "Net-(U4-PB0(PCINT8{slash}XTAL1{slash}CLKI))") (class "Default")
      (node (ref "C41") (pin "2") (pinfunction "2_2") (pintype "passive"))
      (node (ref "U4") (pin "2") (pinfunction "PB0(PCINT8/XTAL1/CLKI)_2") (pintype "bidirectional"))
      (node (ref "X2") (pin "1") (pinfunction "1_1") (pintype "passive"))
    )
    (net (code "69") (name "Net-(U4-PB1(PCINT9{slash}XTAL2))") (class "Default")
      (node (ref "C42") (pin "2") (pinfunction "2_2") (pintype "passive"))
      (node (ref "U4") (pin "3") (pinfunction "PB1(PCINT9/XTAL2)_3") (pintype "bidirectional"))
      (node (ref "X2") (pin "3") (pinfunction "2_3") (pintype "passive"))
    )
    (net (code "70") (name "Net-(U4-PB2(PCINT10{slash}INT0{slash}OC0A{slash}CKOUT))") (class "Default")
      (node (ref "PROG") (pin "3") (pinfunction "P$2_3") (pintype "bidirectional"))
      (node (ref "PROG") (pin "4") (pinfunction "P$2_4") (pintype "bidirectional"))
      (node (ref "U4") (pin "5") (pinfunction "PB2(PCINT10/INT0/OC0A/CKOUT)_5") (pintype "bidirectional"))
    )
    (net (code "71") (name "Net-(U5-AVDD)") (class "Default")
      (node (ref "C38") (pin "1") (pinfunction "1_1") (pintype "passive"))
      (node (ref "U5") (pin "24") (pinfunction "AVDD_24") (pintype "bidirectional"))
    )
    (net (code "72") (name "Net-(U5-DVDD)") (class "Default")
      (node (ref "C39") (pin "1") (pinfunction "1_1") (pintype "passive"))
      (node (ref "U5") (pin "29") (pinfunction "DVDD_29") (pintype "bidirectional"))
    )
    (net (code "73") (name "Net-(U5-IN1_L)") (class "Default")
      (node (ref "C34") (pin "2") (pinfunction "2_2") (pintype "passive"))
      (node (ref "U5") (pin "13") (pinfunction "IN1_L_13") (pintype "bidirectional"))
    )
    (net (code "74") (name "Net-(U5-IN1_R)") (class "Default")
      (node (ref "C33") (pin "2") (pinfunction "2_2") (pintype "passive"))
      (node (ref "U5") (pin "14") (pinfunction "IN1_R_14") (pintype "bidirectional"))
    )
    (net (code "75") (name "Net-(U5-LOL)") (class "Default")
      (node (ref "C31") (pin "1") (pinfunction "1_1") (pintype "passive"))
      (node (ref "U5") (pin "22") (pinfunction "LOL_22") (pintype "bidirectional"))
    )
    (net (code "76") (name "Net-(U5-LOR)") (class "Default")
      (node (ref "C32") (pin "1") (pinfunction "1_1") (pintype "passive"))
      (node (ref "U5") (pin "23") (pinfunction "LOR_23") (pintype "bidirectional"))
    )
    (net (code "77") (name "Net-(U5-REF)") (class "Default")
      (node (ref "C40") (pin "1") (pinfunction "1_1") (pintype "passive"))
      (node (ref "U5") (pin "18") (pinfunction "REF_18") (pintype "bidirectional"))
    )
    (net (code "78") (name "unconnected-(IN-L_SW-Pad5)") (class "Default")
      (node (ref "IN") (pin "5") (pinfunction "L_SW_5") (pintype "bidirectional"))
    )
    (net (code "79") (name "unconnected-(IN-R_SW-Pad3)") (class "Default")
      (node (ref "IN") (pin "3") (pinfunction "R_SW_3") (pintype "bidirectional"))
    )
    (net (code "80") (name "unconnected-(J2-Pad3)") (class "Default")
      (node (ref "J2") (pin "3") (pinfunction "3_3") (pintype "bidirectional"))
    )
    (net (code "81") (name "unconnected-(J2-Pad4)") (class "Default")
      (node (ref "J2") (pin "4") (pinfunction "4_4") (pintype "bidirectional"))
    )
    (net (code "82") (name "unconnected-(J2-Pad9)") (class "Default")
      (node (ref "J2") (pin "9") (pinfunction "9_9") (pintype "bidirectional"))
    )
    (net (code "83") (name "unconnected-(OUT-L_SW-Pad5)") (class "Default")
      (node (ref "OUT") (pin "5") (pinfunction "L_SW_5") (pintype "bidirectional"))
    )
    (net (code "84") (name "unconnected-(OUT-R_SW-Pad3)") (class "Default")
      (node (ref "OUT") (pin "3") (pinfunction "R_SW_3") (pintype "bidirectional"))
    )
    (net (code "85") (name "unconnected-(U2-SCL{slash}GIO10-Pad32)") (class "Default")
      (node (ref "U2") (pin "32") (pinfunction "SCL/GIO10_32") (pintype "bidirectional"))
    )
    (net (code "86") (name "unconnected-(U2-SDA{slash}GIO11-Pad33)") (class "Default")
      (node (ref "U2") (pin "33") (pinfunction "SDA/GIO11_33") (pintype "bidirectional"))
    )
    (net (code "87") (name "unconnected-(U3-RXTX-Pad3)") (class "Default")
      (node (ref "U3") (pin "3") (pinfunction "RXTX_3") (pintype "bidirectional"))
    )
    (net (code "88") (name "unconnected-(U5-GPIO{slash}MFP5-Pad32)") (class "Default")
      (node (ref "U5") (pin "32") (pinfunction "GPIO/MFP5_32") (pintype "bidirectional"))
    )
    (net (code "89") (name "unconnected-(U5-HPL-Pad25)") (class "Default")
      (node (ref "U5") (pin "25") (pinfunction "HPL_25") (pintype "bidirectional"))
    )
    (net (code "90") (name "unconnected-(U5-HPR-Pad27)") (class "Default")
      (node (ref "U5") (pin "27") (pinfunction "HPR_27") (pintype "bidirectional"))
    )
    (net (code "91") (name "unconnected-(U5-IN2_L-Pad15)") (class "Default")
      (node (ref "U5") (pin "15") (pinfunction "IN2_L_15") (pintype "bidirectional"))
    )
    (net (code "92") (name "unconnected-(U5-IN2_R-Pad16)") (class "Default")
      (node (ref "U5") (pin "16") (pinfunction "IN2_R_16") (pintype "bidirectional"))
    )
    (net (code "93") (name "unconnected-(U5-IN3_L-Pad20)") (class "Default")
      (node (ref "U5") (pin "20") (pinfunction "IN3_L_20") (pintype "bidirectional"))
    )
    (net (code "94") (name "unconnected-(U5-IN3_R-Pad21)") (class "Default")
      (node (ref "U5") (pin "21") (pinfunction "IN3_R_21") (pintype "bidirectional"))
    )
    (net (code "95") (name "unconnected-(U5-MICBIAS-Pad19)") (class "Default")
      (node (ref "U5") (pin "19") (pinfunction "MICBIAS_19") (pintype "bidirectional"))
    )
    (net (code "96") (name "unconnected-(USB-ID-Pad4)") (class "Default")
      (node (ref "USB") (pin "4") (pinfunction "ID_4") (pintype "bidirectional"))
    )
  )
)
